# Sensors.net
KiCad netlist of a schematic drawn in Altium Designer
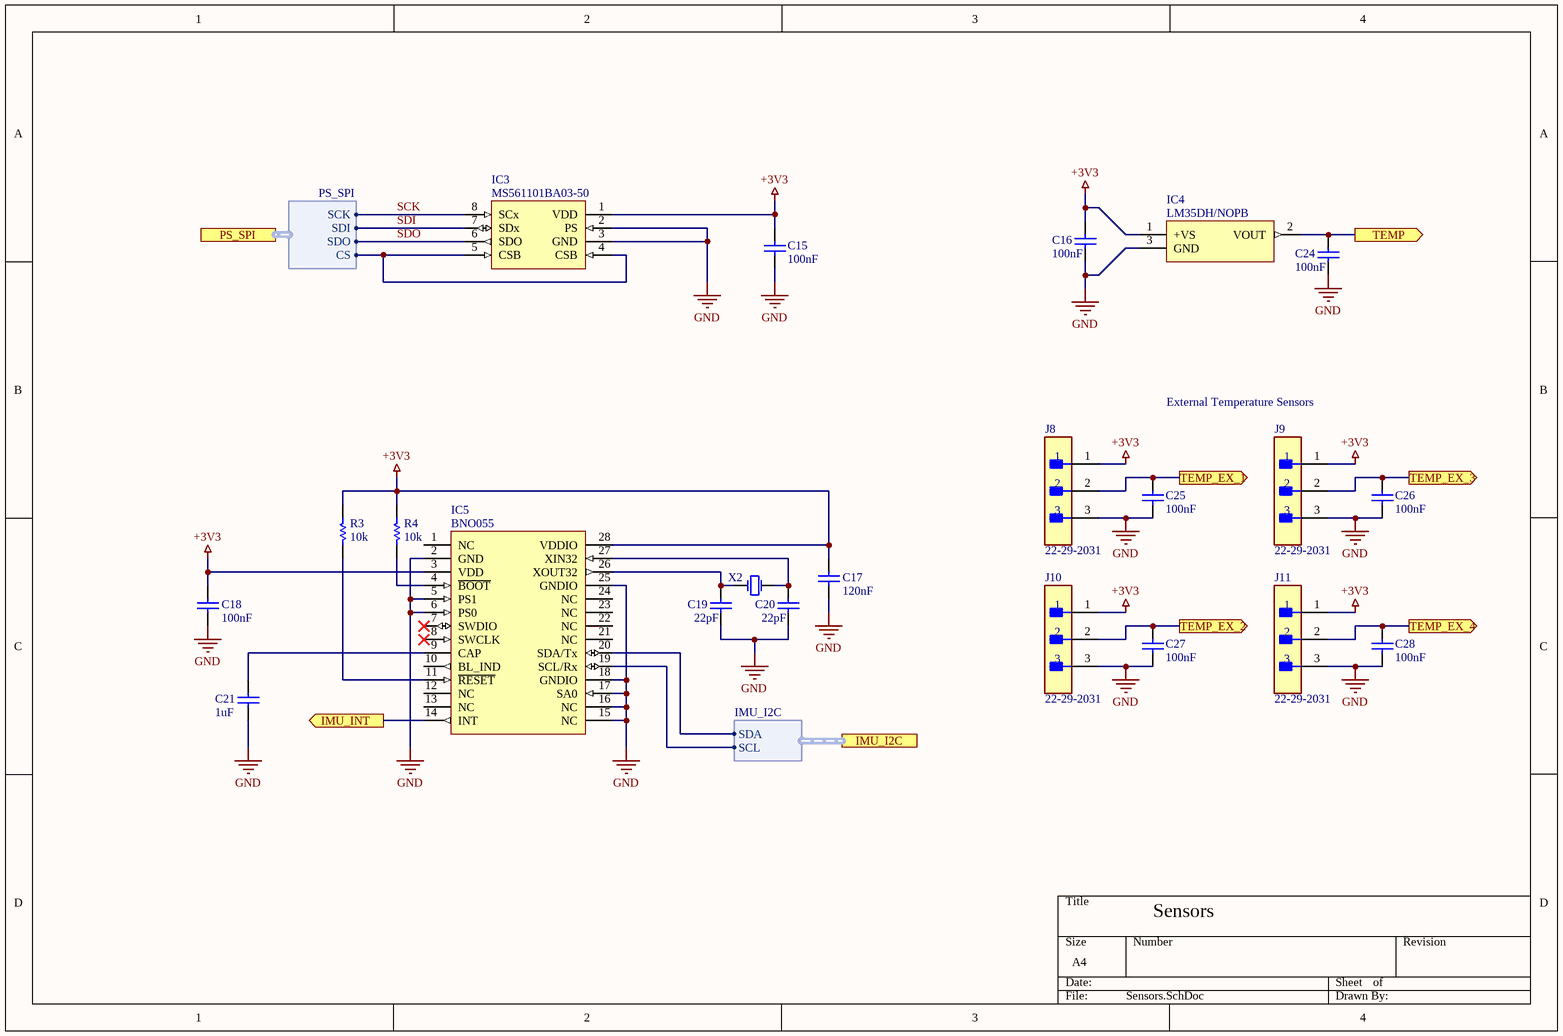
[diagram p0: Sensors.SchDoc]

(export (version "E")
  (design (tool "Eeschema 10.0.6"))
  (components
    (comp (ref "C15")
      (value "100nF")
      (footprint "CAPC1608X10N")
      (description "Cap Ceramic 0.1uF 50V X7R 20% SMD 0603 125C T/R")
      (fields (field (name "TOLERANCE") "20%") (field (name "Comment") "C0603C104M5RACTU"))
      (libsource (lib "UWA Aerospace") (part "C0603C104M5RACTU"))
    )
    (comp (ref "C16")
      (value "C0603C104M5RACTU")
      (footprint "CAPC1608X10N")
      (description "Cap Ceramic 0.1uF 50V X7R 20% SMD 0603 125C T/R")
      (fields (field (name "CAPACITANCE") "100nF") (field (name "TOLERANCE") "20%"))
      (libsource (lib "UWA Aerospace") (part "C0603C104M5RACTU"))
    )
    (comp (ref "C17")
      (value "120nF")
      (footprint "CAPC1608X10N")
      (fields (field (name "TOLERANCE") "10%") (field (name "Comment") "C0603C124K4RACTU"))
      (libsource (lib "UWA Aerospace") (part "Capacitor - Non-polar"))
    )
    (comp (ref "C18")
      (value "100nF")
      (footprint "CAPC1608X10N")
      (description "Cap Ceramic 0.1uF 50V X7R 20% SMD 0603 125C T/R")
      (fields (field (name "TOLERANCE") "20%") (field (name "Comment") "C0603C104M5RACTU"))
      (libsource (lib "UWA Aerospace") (part "C0603C104M5RACTU"))
    )
    (comp (ref "C19")
      (value "22pF")
      (footprint "CAPC1005X05N")
      (description "CAP CER 22PF 50V C0G/NP0 0402")
      (fields (field (name "TOLERANCE") "10%") (field (name "Comment") "C0402C220K5GACTU"))
      (libsource (lib "UWA Aerospace") (part "C0603C104M5RACTU"))
    )
    (comp (ref "C20")
      (value "22pF")
      (footprint "CAPC1005X05N")
      (description "CAP CER 22PF 50V C0G/NP0 0402")
      (fields (field (name "TOLERANCE") "10%") (field (name "Comment") "C0402C220K5GACTU"))
      (libsource (lib "UWA Aerospace") (part "C0603C104M5RACTU"))
    )
    (comp (ref "C21")
      (value "1uF")
      (footprint "CAPC1608X10N")
      (description "Cap Ceramic 1uF 10V X5R 10% SMD 0603 85°C Paper T/R")
      (fields (field (name "TOLERANCE") "10%") (field (name "VOLTAGE") "10V"))
      (libsource (lib "UWA Aerospace") (part "C0603C104M5RACTU"))
    )
    (comp (ref "C24")
      (value "C0603C104M5RACTU")
      (footprint "CAPC1608X10N")
      (description "Cap Ceramic 0.1uF 50V X7R 20% SMD 0603 125C T/R")
      (fields (field (name "CAPACITANCE") "100nF") (field (name "TOLERANCE") "20%"))
      (libsource (lib "UWA Aerospace") (part "C0603C104M5RACTU"))
    )
    (comp (ref "C25")
      (value "100nF")
      (footprint "CAPC1608X10N")
      (description "Cap Ceramic 0.1uF 50V X7R 20% SMD 0603 125C T/R")
      (fields (field (name "TOLERANCE") "20%") (field (name "Comment") "C0603C104M5RACTU"))
      (libsource (lib "UWA Aerospace") (part "C0603C104M5RACTU"))
    )
    (comp (ref "C26")
      (value "100nF")
      (footprint "CAPC1608X10N")
      (description "Cap Ceramic 0.1uF 50V X7R 20% SMD 0603 125C T/R")
      (fields (field (name "TOLERANCE") "20%") (field (name "Comment") "C0603C104M5RACTU"))
      (libsource (lib "UWA Aerospace") (part "C0603C104M5RACTU"))
    )
    (comp (ref "C27")
      (value "100nF")
      (footprint "CAPC1608X10N")
      (description "Cap Ceramic 0.1uF 50V X7R 20% SMD 0603 125C T/R")
      (fields (field (name "TOLERANCE") "20%") (field (name "Comment") "C0603C104M5RACTU"))
      (libsource (lib "UWA Aerospace") (part "C0603C104M5RACTU"))
    )
    (comp (ref "C28")
      (value "100nF")
      (footprint "CAPC1608X10N")
      (description "Cap Ceramic 0.1uF 50V X7R 20% SMD 0603 125C T/R")
      (fields (field (name "TOLERANCE") "20%") (field (name "Comment") "C0603C104M5RACTU"))
      (libsource (lib "UWA Aerospace") (part "C0603C104M5RACTU"))
    )
    (comp (ref "IC3")
      (value "MS561101BA03-50")
      (footprint "MS561101BA03-50-Footprint-1")
      (description "SENSOR SOLUTIONS - TE CONNECTIVITY - MS561101BA03-50 - MS5611-BT M-CAPS 3X5X1MM T&R / T&R")
      (libsource (lib "UWA Aerospace") (part "MS561101BA03-50"))
    )
    (comp (ref "IC4")
      (value "LM35DH/NOPB")
      (footprint "LM35DH_NOPB-Footprint-1")
      (description "TEXAS INSTRUMENTS LM35DH/NOPB Temperature Sensor IC, Voltage,  0.6C, 0 C, +100 C, TO-46, 3 Pins")
      (libsource (lib "UWA Aerospace") (part "LM35DH_NOPB"))
    )
    (comp (ref "IC5")
      (value "BNO055")
      (footprint "BNO055-Footprint-1")
      (description "IMU ACCEL/GYRO/MAG I2C 28LGA")
      (libsource (lib "UWA Aerospace") (part "BNO055"))
    )
    (comp (ref "J8")
      (value "22-29-2031")
      (footprint "FP-22-29-2031-MFG")
      (description "CONN HEADER VERT 3POS 2.54MM")
      (libsource (lib "Altium Content Vault") (part "0d3f023dd272f625e17a2be33dea85f"))
    )
    (comp (ref "J9")
      (value "22-29-2031")
      (footprint "FP-22-29-2031-MFG")
      (description "CONN HEADER VERT 3POS 2.54MM")
      (libsource (lib "Altium Content Vault") (part "0d3f023dd272f625e17a2be33dea85f"))
    )
    (comp (ref "J10")
      (value "22-29-2031")
      (footprint "FP-22-29-2031-MFG")
      (description "CONN HEADER VERT 3POS 2.54MM")
      (libsource (lib "Altium Content Vault") (part "0d3f023dd272f625e17a2be33dea85f"))
    )
    (comp (ref "J11")
      (value "22-29-2031")
      (footprint "FP-22-29-2031-MFG")
      (description "CONN HEADER VERT 3POS 2.54MM")
      (libsource (lib "Altium Content Vault") (part "0d3f023dd272f625e17a2be33dea85f"))
    )
    (comp (ref "R3")
      (value "10k")
      (footprint "RESC1608X06N")
      (fields (field (name "TOLERANCE") "1%") (field (name "Comment") "CRCW060310K0FKEA"))
      (libsource (lib "UWA Aerospace") (part "CRCW060310K0FKEA"))
    )
    (comp (ref "R4")
      (value "10k")
      (footprint "RESC1608X06N")
      (fields (field (name "TOLERANCE") "1%") (field (name "Comment") "CRCW060310K0FKEA"))
      (libsource (lib "UWA Aerospace") (part "CRCW060310K0FKEA"))
    )
    (comp (ref "X2")
      (value "ABS07-32.768KHZ-T")
      (footprint "ABS07-32.768KHZ-T-Footprint-1")
      (description "Crystal; Ulta-Mini; 3.2 x 1.5 x 0.9mm; 32.768KHZ; 12.5pf; 20ppm -40+85C; SMD; T/R")
      (fields (field (name "TOLERANCE") "20ppm"))
      (libsource (lib "UWA Aerospace") (part "ABS07-32.768KHZ-T"))
    )
  )
  (nets
    (net (code "3") (name "+3V3") (class "Default")
      (node (ref "C15") (pin "2") (pinfunction "2_2") (pintype "passive"))
      (node (ref "C16") (pin "2") (pinfunction "2_2") (pintype "passive"))
      (node (ref "C17") (pin "2") (pinfunction "2_2") (pintype "passive"))
      (node (ref "C18") (pin "2") (pinfunction "2_2") (pintype "passive"))
      (node (ref "IC3") (pin "1") (pinfunction "VDD_1") (pintype "power_in"))
      (node (ref "IC4") (pin "1") (pinfunction "+VS_1") (pintype "power_in"))
      (node (ref "IC5") (pin "28") (pinfunction "VDDIO_28") (pintype "power_in"))
      (node (ref "IC5") (pin "3") (pinfunction "VDD_3") (pintype "power_in"))
      (node (ref "J10") (pin "1") (pinfunction "1_1") (pintype "passive"))
      (node (ref "J11") (pin "1") (pinfunction "1_1") (pintype "passive"))
      (node (ref "J8") (pin "1") (pinfunction "1_1") (pintype "passive"))
      (node (ref "J9") (pin "1") (pinfunction "1_1") (pintype "passive"))
      (node (ref "R3") (pin "2") (pinfunction "2_2") (pintype "passive"))
      (node (ref "R4") (pin "2") (pinfunction "2_2") (pintype "passive"))
    )
    (net (code "4") (name "/CS") (class "Default")
      (node (ref "IC3") (pin "4") (pinfunction "CSB_4") (pintype "input"))
      (node (ref "IC3") (pin "5") (pinfunction "CSB_5") (pintype "input"))
    )
    (net (code "5") (name "/IMU_INT") (class "Default")
      (node (ref "IC5") (pin "14") (pinfunction "INT_14") (pintype "output"))
    )
    (net (code "6") (name "/SCK") (class "Default")
      (node (ref "IC3") (pin "8") (pinfunction "SCx_8") (pintype "input"))
    )
    (net (code "7") (name "/SCL") (class "Default")
      (node (ref "IC5") (pin "19") (pinfunction "SCL/Rx_19") (pintype "bidirectional"))
    )
    (net (code "8") (name "/SDA") (class "Default")
      (node (ref "IC5") (pin "20") (pinfunction "SDA/Tx_20") (pintype "bidirectional"))
    )
    (net (code "9") (name "/SDI") (class "Default")
      (node (ref "IC3") (pin "7") (pinfunction "SDx_7") (pintype "bidirectional"))
    )
    (net (code "10") (name "/SDO") (class "Default")
      (node (ref "IC3") (pin "6") (pinfunction "SDO_6") (pintype "output"))
    )
    (net (code "11") (name "/TEMP") (class "Default")
      (node (ref "C24") (pin "2") (pinfunction "2_2") (pintype "passive"))
      (node (ref "IC4") (pin "2") (pinfunction "VOUT_2") (pintype "output"))
    )
    (net (code "12") (name "/TEMP_EX_1") (class "Default")
      (node (ref "C25") (pin "2") (pinfunction "2_2") (pintype "passive"))
      (node (ref "J8") (pin "2") (pinfunction "2_2") (pintype "passive"))
    )
    (net (code "13") (name "/TEMP_EX_2") (class "Default")
      (node (ref "C27") (pin "2") (pinfunction "2_2") (pintype "passive"))
      (node (ref "J10") (pin "2") (pinfunction "2_2") (pintype "passive"))
    )
    (net (code "14") (name "/TEMP_EX_3") (class "Default")
      (node (ref "C26") (pin "2") (pinfunction "2_2") (pintype "passive"))
      (node (ref "J9") (pin "2") (pinfunction "2_2") (pintype "passive"))
    )
    (net (code "15") (name "/TEMP_EX_4") (class "Default")
      (node (ref "C28") (pin "2") (pinfunction "2_2") (pintype "passive"))
      (node (ref "J11") (pin "2") (pinfunction "2_2") (pintype "passive"))
    )
    (net (code "18") (name "GND") (class "Default")
      (node (ref "C15") (pin "1") (pinfunction "1_1") (pintype "passive"))
      (node (ref "C16") (pin "1") (pinfunction "1_1") (pintype "passive"))
      (node (ref "C17") (pin "1") (pinfunction "1_1") (pintype "passive"))
      (node (ref "C18") (pin "1") (pinfunction "1_1") (pintype "passive"))
      (node (ref "C19") (pin "1") (pinfunction "1_1") (pintype "passive"))
      (node (ref "C20") (pin "1") (pinfunction "1_1") (pintype "passive"))
      (node (ref "C21") (pin "1") (pinfunction "1_1") (pintype "passive"))
      (node (ref "C24") (pin "1") (pinfunction "1_1") (pintype "passive"))
      (node (ref "C25") (pin "1") (pinfunction "1_1") (pintype "passive"))
      (node (ref "C26") (pin "1") (pinfunction "1_1") (pintype "passive"))
      (node (ref "C27") (pin "1") (pinfunction "1_1") (pintype "passive"))
      (node (ref "C28") (pin "1") (pinfunction "1_1") (pintype "passive"))
      (node (ref "IC3") (pin "2") (pinfunction "PS_2") (pintype "input"))
      (node (ref "IC3") (pin "3") (pinfunction "GND_3") (pintype "power_in"))
      (node (ref "IC4") (pin "3") (pinfunction "GND_3") (pintype "power_in"))
      (node (ref "IC5") (pin "15") (pinfunction "NC_15") (pintype "power_in"))
      (node (ref "IC5") (pin "16") (pinfunction "NC_16") (pintype "power_in"))
      (node (ref "IC5") (pin "17") (pinfunction "SA0_17") (pintype "input"))
      (node (ref "IC5") (pin "18") (pinfunction "GNDIO_18") (pintype "power_in"))
      (node (ref "IC5") (pin "2") (pinfunction "GND_2") (pintype "power_in"))
      (node (ref "IC5") (pin "25") (pinfunction "GNDIO_25") (pintype "power_in"))
      (node (ref "IC5") (pin "5") (pinfunction "PS1_5") (pintype "input"))
      (node (ref "IC5") (pin "6") (pinfunction "PS0_6") (pintype "input"))
      (node (ref "J10") (pin "3") (pinfunction "3_3") (pintype "passive"))
      (node (ref "J11") (pin "3") (pinfunction "3_3") (pintype "passive"))
      (node (ref "J8") (pin "3") (pinfunction "3_3") (pintype "passive"))
      (node (ref "J9") (pin "3") (pinfunction "3_3") (pintype "passive"))
    )
    (net (code "19") (name "Net-(IC5-CAP)") (class "Default")
      (node (ref "C21") (pin "2") (pinfunction "2_2") (pintype "passive"))
      (node (ref "IC5") (pin "9") (pinfunction "CAP_9") (pintype "passive"))
    )
    (net (code "20") (name "Net-(IC5-XIN32)") (class "Default")
      (node (ref "C20") (pin "2") (pinfunction "2_2") (pintype "passive"))
      (node (ref "IC5") (pin "27") (pinfunction "XIN32_27") (pintype "input"))
      (node (ref "X2") (pin "2") (pinfunction "OSC2_2") (pintype "passive"))
    )
    (net (code "21") (name "Net-(IC5-XOUT32)") (class "Default")
      (node (ref "C19") (pin "2") (pinfunction "2_2") (pintype "passive"))
      (node (ref "IC5") (pin "26") (pinfunction "XOUT32_26") (pintype "output"))
      (node (ref "X2") (pin "1") (pinfunction "OSC1_1") (pintype "passive"))
    )
    (net (code "22") (name "Net-(IC5-~{BOOT})") (class "Default")
      (node (ref "IC5") (pin "4") (pinfunction "~{BOOT}_4") (pintype "input"))
      (node (ref "R4") (pin "1") (pinfunction "1_1") (pintype "passive"))
    )
    (net (code "23") (name "Net-(IC5-~{RESET})") (class "Default")
      (node (ref "IC5") (pin "11") (pinfunction "~{RESET}_11") (pintype "input"))
      (node (ref "R3") (pin "1") (pinfunction "1_1") (pintype "passive"))
    )
    (net (code "24") (name "unconnected-(IC5-BL_IND-Pad10)") (class "Default")
      (node (ref "IC5") (pin "10") (pinfunction "BL_IND_10") (pintype "output"))
    )
    (net (code "25") (name "unconnected-(IC5-NC-Pad1)") (class "Default")
      (node (ref "IC5") (pin "1") (pinfunction "NC_1") (pintype "passive"))
    )
    (net (code "26") (name "unconnected-(IC5-NC-Pad12)") (class "Default")
      (node (ref "IC5") (pin "12") (pinfunction "NC_12") (pintype "passive"))
    )
    (net (code "27") (name "unconnected-(IC5-NC-Pad13)") (class "Default")
      (node (ref "IC5") (pin "13") (pinfunction "NC_13") (pintype "passive"))
    )
    (net (code "28") (name "unconnected-(IC5-NC-Pad21)") (class "Default")
      (node (ref "IC5") (pin "21") (pinfunction "NC_21") (pintype "passive"))
    )
    (net (code "29") (name "unconnected-(IC5-NC-Pad22)") (class "Default")
      (node (ref "IC5") (pin "22") (pinfunction "NC_22") (pintype "passive"))
    )
    (net (code "30") (name "unconnected-(IC5-NC-Pad23)") (class "Default")
      (node (ref "IC5") (pin "23") (pinfunction "NC_23") (pintype "passive"))
    )
    (net (code "31") (name "unconnected-(IC5-NC-Pad24)") (class "Default")
      (node (ref "IC5") (pin "24") (pinfunction "NC_24") (pintype "passive"))
    )
    (net (code "32") (name "unconnected-(IC5-SWCLK-Pad8)") (class "Default")
      (node (ref "IC5") (pin "8") (pinfunction "SWCLK_8") (pintype "input+no_connect"))
    )
    (net (code "33") (name "unconnected-(IC5-SWDIO-Pad7)") (class "Default")
      (node (ref "IC5") (pin "7") (pinfunction "SWDIO_7") (pintype "bidirectional+no_connect"))
    )
  )
)
